# SolderDispenser_v1_0.net
KiCad netlist of a schematic drawn in EAGLE
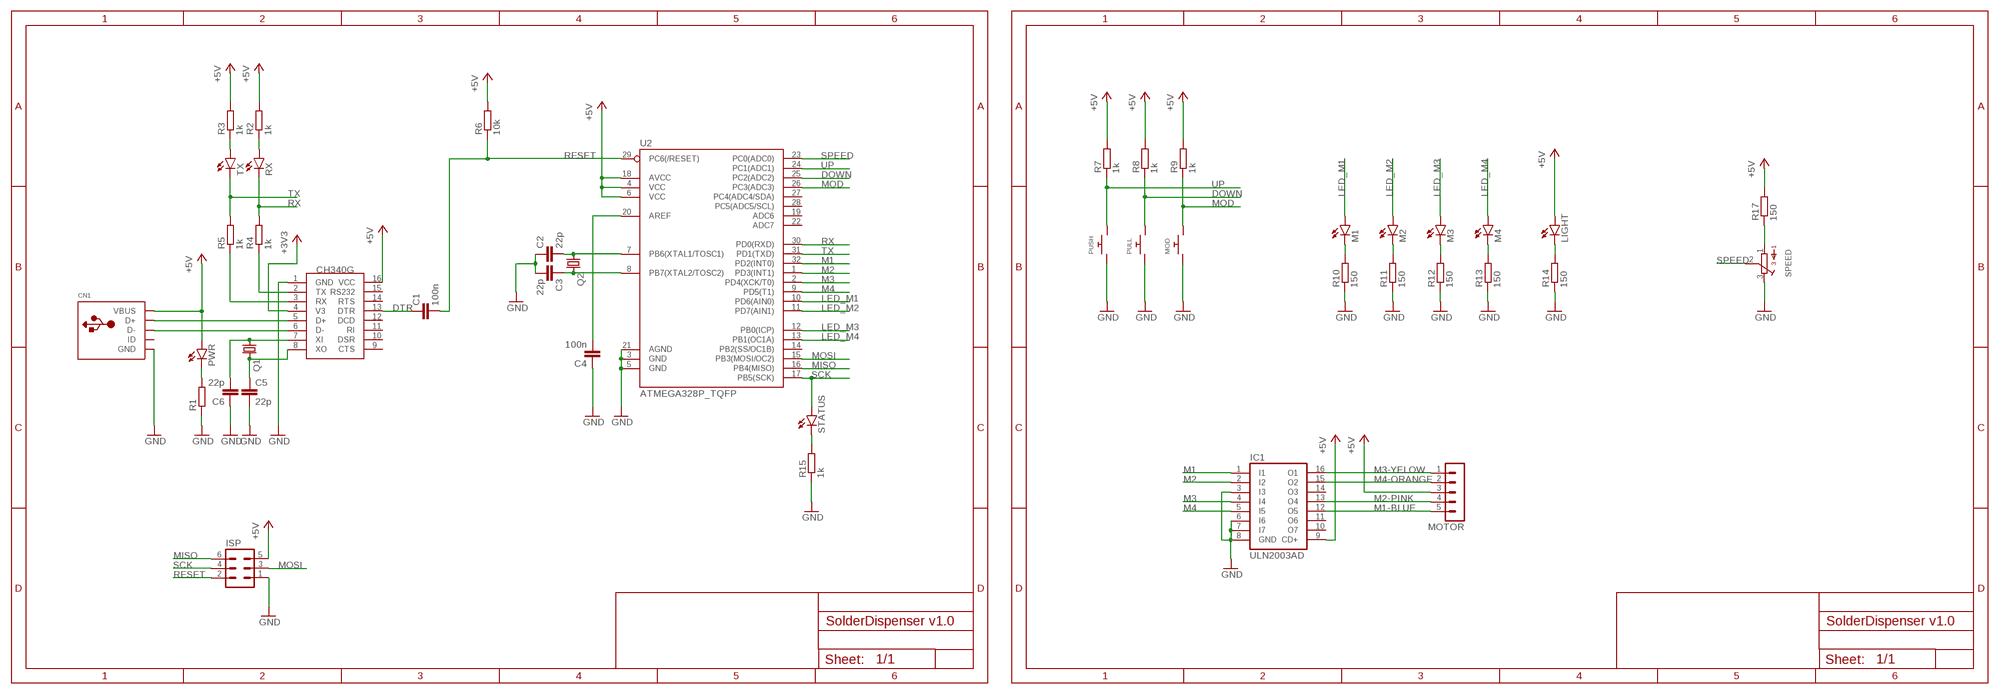
[diagram p0: schematic, sheet 1]

(export (version "E")
  (design (tool "Eeschema 10.0.6"))
  (components
    (comp (ref "C1")
      (value "100n")
      (footprint "eagle-import:C0805")
      (libsource (lib "eagle-import") (part "C-EUC0805"))
    )
    (comp (ref "C2")
      (value "22p")
      (footprint "eagle-import:C0805")
      (libsource (lib "eagle-import") (part "C-EUC0805"))
    )
    (comp (ref "C3")
      (value "22p")
      (footprint "eagle-import:C0805")
      (libsource (lib "eagle-import") (part "C-EUC0805"))
    )
    (comp (ref "C4")
      (value "100n")
      (footprint "eagle-import:C0805")
      (libsource (lib "eagle-import") (part "C-EUC0805"))
    )
    (comp (ref "C5")
      (value "22p")
      (footprint "eagle-import:C0805")
      (libsource (lib "eagle-import") (part "C-EUC0805"))
    )
    (comp (ref "C6")
      (value "22p")
      (footprint "eagle-import:C0805")
      (libsource (lib "eagle-import") (part "C-EUC0805"))
    )
    (comp (ref "CN1")
      (value "USBMOLEX")
      (footprint "eagle-import:USB-MINIB-THM-MOLEX")
      (libsource (lib "eagle-import") (part "USBMOLEX"))
    )
    (comp (ref "IC1")
      (value "ULN2003AD")
      (footprint "eagle-import:SO16")
      (libsource (lib "eagle-import") (part "ULN2003AD"))
    )
    (comp (ref "ISP")
      (value "MA03-2")
      (footprint "eagle-import:MA03-2")
      (libsource (lib "eagle-import") (part "MA03-2"))
    )
    (comp (ref "LIGHT")
      (value "LED5MM")
      (footprint "eagle-import:LED5MM")
      (libsource (lib "eagle-import") (part "LED5MM"))
    )
    (comp (ref "M1")
      (value "LEDSML0805")
      (footprint "eagle-import:SML0805")
      (libsource (lib "eagle-import") (part "LEDSML0805"))
    )
    (comp (ref "M2")
      (value "LEDSML0805")
      (footprint "eagle-import:SML0805")
      (libsource (lib "eagle-import") (part "LEDSML0805"))
    )
    (comp (ref "M3")
      (value "LEDSML0805")
      (footprint "eagle-import:SML0805")
      (libsource (lib "eagle-import") (part "LEDSML0805"))
    )
    (comp (ref "M4")
      (value "LEDSML0805")
      (footprint "eagle-import:SML0805")
      (libsource (lib "eagle-import") (part "LEDSML0805"))
    )
    (comp (ref "MOD")
      (value "SWITCH_PUSHBUTTONEVQ-PE")
      (footprint "eagle-import:TACT_PANA-EVQ")
      (libsource (lib "eagle-import") (part "SWITCH_PUSHBUTTONEVQ-PE"))
    )
    (comp (ref "MOTOR")
      (value "MA05-1")
      (footprint "eagle-import:MA05-1")
      (libsource (lib "eagle-import") (part "MA05-1"))
    )
    (comp (ref "PULL")
      (value "SWITCH_PUSHBUTTONEVQ-PE")
      (footprint "eagle-import:TACT_PANA-EVQ")
      (libsource (lib "eagle-import") (part "SWITCH_PUSHBUTTONEVQ-PE"))
    )
    (comp (ref "PUSH")
      (value "SWITCH_PUSHBUTTONEVQ-PE")
      (footprint "eagle-import:TACT_PANA-EVQ")
      (libsource (lib "eagle-import") (part "SWITCH_PUSHBUTTONEVQ-PE"))
    )
    (comp (ref "PWR")
      (value "LEDSML0805")
      (footprint "eagle-import:SML0805")
      (libsource (lib "eagle-import") (part "LEDSML0805"))
    )
    (comp (ref "Q1")
      (value "CRYSTALHC49UP")
      (footprint "eagle-import:HC49UP")
      (libsource (lib "eagle-import") (part "CRYSTALHC49UP"))
    )
    (comp (ref "Q2")
      (value "CRYSTALHC49UP")
      (footprint "eagle-import:HC49UP")
      (libsource (lib "eagle-import") (part "CRYSTALHC49UP"))
    )
    (comp (ref "R1")
      (value "R-EU_R0805")
      (footprint "eagle-import:R0805")
      (libsource (lib "eagle-import") (part "R-EU_R0805"))
    )
    (comp (ref "R2")
      (value "1k")
      (footprint "eagle-import:R0805")
      (libsource (lib "eagle-import") (part "R-EU_R0805"))
    )
    (comp (ref "R3")
      (value "1k")
      (footprint "eagle-import:R0805")
      (libsource (lib "eagle-import") (part "R-EU_R0805"))
    )
    (comp (ref "R4")
      (value "1k")
      (footprint "eagle-import:R0805")
      (libsource (lib "eagle-import") (part "R-EU_R0805"))
    )
    (comp (ref "R5")
      (value "1k")
      (footprint "eagle-import:R0805")
      (libsource (lib "eagle-import") (part "R-EU_R0805"))
    )
    (comp (ref "R6")
      (value "10k")
      (footprint "eagle-import:R0805")
      (libsource (lib "eagle-import") (part "R-EU_R0805"))
    )
    (comp (ref "R7")
      (value "1k")
      (footprint "eagle-import:R0805")
      (libsource (lib "eagle-import") (part "R-EU_R0805"))
    )
    (comp (ref "R8")
      (value "1k")
      (footprint "eagle-import:R0805")
      (libsource (lib "eagle-import") (part "R-EU_R0805"))
    )
    (comp (ref "R9")
      (value "1k")
      (footprint "eagle-import:R0805")
      (libsource (lib "eagle-import") (part "R-EU_R0805"))
    )
    (comp (ref "R10")
      (value "150")
      (footprint "eagle-import:R0805")
      (libsource (lib "eagle-import") (part "R-EU_R0805"))
    )
    (comp (ref "R11")
      (value "150")
      (footprint "eagle-import:R0805")
      (libsource (lib "eagle-import") (part "R-EU_R0805"))
    )
    (comp (ref "R12")
      (value "150")
      (footprint "eagle-import:R0805")
      (libsource (lib "eagle-import") (part "R-EU_R0805"))
    )
    (comp (ref "R13")
      (value "150")
      (footprint "eagle-import:R0805")
      (libsource (lib "eagle-import") (part "R-EU_R0805"))
    )
    (comp (ref "R14")
      (value "150")
      (footprint "eagle-import:R0805")
      (libsource (lib "eagle-import") (part "R-EU_R0805"))
    )
    (comp (ref "R15")
      (value "1k")
      (footprint "eagle-import:R0805")
      (libsource (lib "eagle-import") (part "R-EU_R0805"))
    )
    (comp (ref "R17")
      (value "150")
      (footprint "eagle-import:R0805")
      (libsource (lib "eagle-import") (part "R-EU_R0805"))
    )
    (comp (ref "RX")
      (value "LEDSML0805")
      (footprint "eagle-import:SML0805")
      (libsource (lib "eagle-import") (part "LEDSML0805"))
    )
    (comp (ref "SPEED")
      (value "3362P")
      (footprint "eagle-import:3362P")
      (libsource (lib "eagle-import") (part "3362P"))
    )
    (comp (ref "STATUS")
      (value "LEDSML0805")
      (footprint "eagle-import:SML0805")
      (libsource (lib "eagle-import") (part "LEDSML0805"))
    )
    (comp (ref "TX")
      (value "LEDSML0805")
      (footprint "eagle-import:SML0805")
      (libsource (lib "eagle-import") (part "LEDSML0805"))
    )
    (comp (ref "U$1")
      (value "CH340G")
      (footprint "eagle-import:SOIC16")
      (libsource (lib "eagle-import") (part "CH340G"))
    )
    (comp (ref "U2")
      (value "ATMEGA328P_TQFP")
      (footprint "eagle-import:TQFP32-08")
      (libsource (lib "eagle-import") (part "ATMEGA328P_TQFP"))
    )
  )
  (nets
    (net (code "1") (name "+3V3") (class "Default")
      (node (ref "U$1") (pin "4") (pinfunction "V3_4") (pintype "bidirectional"))
    )
    (net (code "2") (name "+5V") (class "Default")
      (node (ref "CN1") (pin "VBUS") (pinfunction "VBUS_VBUS") (pintype "power_in"))
      (node (ref "IC1") (pin "9") (pinfunction "CD+_9") (pintype "passive"))
      (node (ref "ISP") (pin "5") (pinfunction "5_5") (pintype "passive"))
      (node (ref "LIGHT") (pin "A") (pinfunction "A_A") (pintype "passive"))
      (node (ref "MOTOR") (pin "3") (pinfunction "3_3") (pintype "passive"))
      (node (ref "PWR") (pin "A") (pinfunction "A_A") (pintype "passive"))
      (node (ref "R17") (pin "2") (pinfunction "2_2") (pintype "passive"))
      (node (ref "R2") (pin "2") (pinfunction "2_2") (pintype "passive"))
      (node (ref "R3") (pin "2") (pinfunction "2_2") (pintype "passive"))
      (node (ref "R6") (pin "2") (pinfunction "2_2") (pintype "passive"))
      (node (ref "R7") (pin "2") (pinfunction "2_2") (pintype "passive"))
      (node (ref "R8") (pin "2") (pinfunction "2_2") (pintype "passive"))
      (node (ref "R9") (pin "2") (pinfunction "2_2") (pintype "passive"))
      (node (ref "U$1") (pin "16") (pinfunction "VCC_16") (pintype "bidirectional"))
      (node (ref "U2") (pin "18") (pinfunction "AVCC_18") (pintype "bidirectional"))
      (node (ref "U2") (pin "4") (pinfunction "VCC_4") (pintype "bidirectional"))
      (node (ref "U2") (pin "6") (pinfunction "VCC_6") (pintype "bidirectional"))
    )
    (net (code "3") (name "/DOWN") (class "Default")
      (node (ref "PULL") (pin "P$2") (pinfunction "P$2_P$2") (pintype "passive"))
      (node (ref "R8") (pin "1") (pinfunction "1_1") (pintype "passive"))
      (node (ref "U2") (pin "25") (pinfunction "PC2(ADC2)_25") (pintype "bidirectional"))
    )
    (net (code "4") (name "/DTR") (class "Default")
      (node (ref "C1") (pin "1") (pinfunction "1_1") (pintype "passive"))
      (node (ref "U$1") (pin "13") (pinfunction "DTR_13") (pintype "bidirectional"))
    )
    (net (code "5") (name "/LED_M1") (class "Default")
      (node (ref "M1") (pin "A") (pinfunction "A_A") (pintype "passive"))
      (node (ref "U2") (pin "10") (pinfunction "PD6(AIN0)_10") (pintype "bidirectional"))
    )
    (net (code "6") (name "/LED_M2") (class "Default")
      (node (ref "M2") (pin "A") (pinfunction "A_A") (pintype "passive"))
      (node (ref "U2") (pin "11") (pinfunction "PD7(AIN1)_11") (pintype "bidirectional"))
    )
    (net (code "7") (name "/LED_M3") (class "Default")
      (node (ref "M3") (pin "A") (pinfunction "A_A") (pintype "passive"))
      (node (ref "U2") (pin "12") (pinfunction "PB0(ICP)_12") (pintype "bidirectional"))
    )
    (net (code "8") (name "/LED_M4") (class "Default")
      (node (ref "M4") (pin "A") (pinfunction "A_A") (pintype "passive"))
      (node (ref "U2") (pin "13") (pinfunction "PB1(OC1A)_13") (pintype "bidirectional"))
    )
    (net (code "9") (name "/M1") (class "Default")
      (node (ref "IC1") (pin "1") (pinfunction "I1_1") (pintype "input"))
      (node (ref "U2") (pin "32") (pinfunction "PD2(INT0)_32") (pintype "bidirectional"))
    )
    (net (code "10") (name "/M1-BLUE") (class "Default")
      (node (ref "IC1") (pin "12") (pinfunction "O5_12") (pintype "open_collector"))
      (node (ref "MOTOR") (pin "5") (pinfunction "5_5") (pintype "passive"))
    )
    (net (code "11") (name "/M2") (class "Default")
      (node (ref "IC1") (pin "2") (pinfunction "I2_2") (pintype "input"))
      (node (ref "U2") (pin "1") (pinfunction "PD3(INT1)_1") (pintype "bidirectional"))
    )
    (net (code "12") (name "/M2-PINK") (class "Default")
      (node (ref "IC1") (pin "13") (pinfunction "O4_13") (pintype "open_collector"))
      (node (ref "MOTOR") (pin "4") (pinfunction "4_4") (pintype "passive"))
    )
    (net (code "13") (name "/M3") (class "Default")
      (node (ref "IC1") (pin "4") (pinfunction "I4_4") (pintype "input"))
      (node (ref "U2") (pin "2") (pinfunction "PD4(XCK/T0)_2") (pintype "bidirectional"))
    )
    (net (code "14") (name "/M3-YELOW") (class "Default")
      (node (ref "IC1") (pin "16") (pinfunction "O1_16") (pintype "open_collector"))
      (node (ref "MOTOR") (pin "1") (pinfunction "1_1") (pintype "passive"))
    )
    (net (code "15") (name "/M4") (class "Default")
      (node (ref "IC1") (pin "5") (pinfunction "I5_5") (pintype "input"))
      (node (ref "U2") (pin "9") (pinfunction "PD5(T1)_9") (pintype "bidirectional"))
    )
    (net (code "16") (name "/M4-ORANGE") (class "Default")
      (node (ref "IC1") (pin "15") (pinfunction "O2_15") (pintype "open_collector"))
      (node (ref "MOTOR") (pin "2") (pinfunction "2_2") (pintype "passive"))
    )
    (net (code "17") (name "/MISO") (class "Default")
      (node (ref "ISP") (pin "6") (pinfunction "6_6") (pintype "passive"))
      (node (ref "U2") (pin "16") (pinfunction "PB4(MISO)_16") (pintype "bidirectional"))
    )
    (net (code "18") (name "/MOD") (class "Default")
      (node (ref "MOD") (pin "P$2") (pinfunction "P$2_P$2") (pintype "passive"))
      (node (ref "R9") (pin "1") (pinfunction "1_1") (pintype "passive"))
      (node (ref "U2") (pin "26") (pinfunction "PC3(ADC3)_26") (pintype "bidirectional"))
    )
    (net (code "19") (name "/MOSI") (class "Default")
      (node (ref "ISP") (pin "3") (pinfunction "3_3") (pintype "passive"))
      (node (ref "U2") (pin "15") (pinfunction "PB3(MOSI/OC2)_15") (pintype "bidirectional"))
    )
    (net (code "20") (name "/RESET") (class "Default")
      (node (ref "C1") (pin "2") (pinfunction "2_2") (pintype "passive"))
      (node (ref "ISP") (pin "2") (pinfunction "2_2") (pintype "passive"))
      (node (ref "R6") (pin "1") (pinfunction "1_1") (pintype "passive"))
      (node (ref "U2") (pin "29") (pinfunction "PC6(/RESET)_29") (pintype "bidirectional"))
    )
    (net (code "21") (name "/RX") (class "Default")
      (node (ref "R4") (pin "2") (pinfunction "2_2") (pintype "passive"))
      (node (ref "RX") (pin "C") (pinfunction "C_C") (pintype "passive"))
      (node (ref "U2") (pin "30") (pinfunction "PD0(RXD)_30") (pintype "bidirectional"))
    )
    (net (code "22") (name "/SCK") (class "Default")
      (node (ref "ISP") (pin "4") (pinfunction "4_4") (pintype "passive"))
      (node (ref "STATUS") (pin "A") (pinfunction "A_A") (pintype "passive"))
      (node (ref "U2") (pin "17") (pinfunction "PB5(SCK)_17") (pintype "bidirectional"))
    )
    (net (code "23") (name "/SPEED") (class "Default")
      (node (ref "SPEED") (pin "2") (pinfunction "2_2") (pintype "passive"))
      (node (ref "U2") (pin "23") (pinfunction "PC0(ADC0)_23") (pintype "bidirectional"))
    )
    (net (code "24") (name "/TX") (class "Default")
      (node (ref "R5") (pin "2") (pinfunction "2_2") (pintype "passive"))
      (node (ref "TX") (pin "C") (pinfunction "C_C") (pintype "passive"))
      (node (ref "U2") (pin "31") (pinfunction "PD1(TXD)_31") (pintype "bidirectional"))
    )
    (net (code "25") (name "/UP") (class "Default")
      (node (ref "PUSH") (pin "P$2") (pinfunction "P$2_P$2") (pintype "passive"))
      (node (ref "R7") (pin "1") (pinfunction "1_1") (pintype "passive"))
      (node (ref "U2") (pin "24") (pinfunction "PC1(ADC1)_24") (pintype "bidirectional"))
    )
    (net (code "26") (name "GND") (class "Default")
      (node (ref "C2") (pin "1") (pinfunction "1_1") (pintype "passive"))
      (node (ref "C3") (pin "2") (pinfunction "2_2") (pintype "passive"))
      (node (ref "C4") (pin "1") (pinfunction "1_1") (pintype "passive"))
      (node (ref "C5") (pin "2") (pinfunction "2_2") (pintype "passive"))
      (node (ref "C6") (pin "1") (pinfunction "1_1") (pintype "passive"))
      (node (ref "CN1") (pin "GND") (pinfunction "GND_GND") (pintype "power_in"))
      (node (ref "IC1") (pin "3") (pinfunction "I3_3") (pintype "input"))
      (node (ref "IC1") (pin "6") (pinfunction "I6_6") (pintype "input"))
      (node (ref "IC1") (pin "7") (pinfunction "I7_7") (pintype "input"))
      (node (ref "IC1") (pin "8") (pinfunction "GND_8") (pintype "power_in"))
      (node (ref "ISP") (pin "1") (pinfunction "1_1") (pintype "passive"))
      (node (ref "MOD") (pin "P$1") (pinfunction "P$1_P$1") (pintype "passive"))
      (node (ref "PULL") (pin "P$1") (pinfunction "P$1_P$1") (pintype "passive"))
      (node (ref "PUSH") (pin "P$1") (pinfunction "P$1_P$1") (pintype "passive"))
      (node (ref "R1") (pin "1") (pinfunction "1_1") (pintype "passive"))
      (node (ref "R10") (pin "1") (pinfunction "1_1") (pintype "passive"))
      (node (ref "R11") (pin "1") (pinfunction "1_1") (pintype "passive"))
      (node (ref "R12") (pin "1") (pinfunction "1_1") (pintype "passive"))
      (node (ref "R13") (pin "1") (pinfunction "1_1") (pintype "passive"))
      (node (ref "R14") (pin "1") (pinfunction "1_1") (pintype "passive"))
      (node (ref "R15") (pin "1") (pinfunction "1_1") (pintype "passive"))
      (node (ref "SPEED") (pin "3") (pinfunction "3_3") (pintype "passive"))
      (node (ref "U$1") (pin "1") (pinfunction "GND_1") (pintype "bidirectional"))
      (node (ref "U2") (pin "21") (pinfunction "AGND_21") (pintype "bidirectional"))
      (node (ref "U2") (pin "3") (pinfunction "GND_3") (pintype "bidirectional"))
      (node (ref "U2") (pin "5") (pinfunction "GND_5") (pintype "bidirectional"))
    )
    (net (code "27") (name "Net-(LIGHT-C)") (class "Default")
      (node (ref "LIGHT") (pin "K") (pinfunction "C_K") (pintype "passive"))
      (node (ref "R14") (pin "2") (pinfunction "2_2") (pintype "passive"))
    )
    (net (code "28") (name "Net-(M1-PadC)") (class "Default")
      (node (ref "M1") (pin "C") (pinfunction "C_C") (pintype "passive"))
      (node (ref "R10") (pin "2") (pinfunction "2_2") (pintype "passive"))
    )
    (net (code "29") (name "Net-(M2-PadC)") (class "Default")
      (node (ref "M2") (pin "C") (pinfunction "C_C") (pintype "passive"))
      (node (ref "R11") (pin "2") (pinfunction "2_2") (pintype "passive"))
    )
    (net (code "30") (name "Net-(M3-PadC)") (class "Default")
      (node (ref "M3") (pin "C") (pinfunction "C_C") (pintype "passive"))
      (node (ref "R12") (pin "2") (pinfunction "2_2") (pintype "passive"))
    )
    (net (code "31") (name "Net-(M4-PadC)") (class "Default")
      (node (ref "M4") (pin "C") (pinfunction "C_C") (pintype "passive"))
      (node (ref "R13") (pin "2") (pinfunction "2_2") (pintype "passive"))
    )
    (net (code "32") (name "Net-(PWR-PadC)") (class "Default")
      (node (ref "PWR") (pin "C") (pinfunction "C_C") (pintype "passive"))
      (node (ref "R1") (pin "2") (pinfunction "2_2") (pintype "passive"))
    )
    (net (code "33") (name "Net-(R2-Pad1)") (class "Default")
      (node (ref "R2") (pin "1") (pinfunction "1_1") (pintype "passive"))
      (node (ref "RX") (pin "A") (pinfunction "A_A") (pintype "passive"))
    )
    (net (code "34") (name "Net-(R3-Pad1)") (class "Default")
      (node (ref "R3") (pin "1") (pinfunction "1_1") (pintype "passive"))
      (node (ref "TX") (pin "A") (pinfunction "A_A") (pintype "passive"))
    )
    (net (code "35") (name "Net-(R15-Pad2)") (class "Default")
      (node (ref "R15") (pin "2") (pinfunction "2_2") (pintype "passive"))
      (node (ref "STATUS") (pin "C") (pinfunction "C_C") (pintype "passive"))
    )
    (net (code "36") (name "Net-(R17-Pad1)") (class "Default")
      (node (ref "R17") (pin "1") (pinfunction "1_1") (pintype "passive"))
      (node (ref "SPEED") (pin "1") (pinfunction "1_1") (pintype "passive"))
    )
    (net (code "37") (name "Net-(U$1-D+)") (class "Default")
      (node (ref "CN1") (pin "D+") (pinfunction "D+_D+") (pintype "bidirectional"))
      (node (ref "U$1") (pin "5") (pinfunction "D+_5") (pintype "bidirectional"))
    )
    (net (code "38") (name "Net-(U$1-D-)") (class "Default")
      (node (ref "CN1") (pin "D-") (pinfunction "D-_D-") (pintype "bidirectional"))
      (node (ref "U$1") (pin "6") (pinfunction "D-_6") (pintype "bidirectional"))
    )
    (net (code "39") (name "Net-(U$1-RX)") (class "Default")
      (node (ref "R5") (pin "1") (pinfunction "1_1") (pintype "passive"))
      (node (ref "U$1") (pin "3") (pinfunction "RX_3") (pintype "bidirectional"))
    )
    (net (code "40") (name "Net-(U$1-TX)") (class "Default")
      (node (ref "R4") (pin "1") (pinfunction "1_1") (pintype "passive"))
      (node (ref "U$1") (pin "2") (pinfunction "TX_2") (pintype "bidirectional"))
    )
    (net (code "41") (name "Net-(U$1-XI)") (class "Default")
      (node (ref "C6") (pin "2") (pinfunction "2_2") (pintype "passive"))
      (node (ref "Q1") (pin "1") (pinfunction "1_1") (pintype "passive"))
      (node (ref "U$1") (pin "7") (pinfunction "XI_7") (pintype "bidirectional"))
    )
    (net (code "42") (name "Net-(U$1-XO)") (class "Default")
      (node (ref "C5") (pin "1") (pinfunction "1_1") (pintype "passive"))
      (node (ref "Q1") (pin "2") (pinfunction "2_2") (pintype "passive"))
      (node (ref "U$1") (pin "8") (pinfunction "XO_8") (pintype "bidirectional"))
    )
    (net (code "43") (name "Net-(U2-AREF)") (class "Default")
      (node (ref "C4") (pin "2") (pinfunction "2_2") (pintype "passive"))
      (node (ref "U2") (pin "20") (pinfunction "AREF_20") (pintype "bidirectional"))
    )
    (net (code "44") (name "Net-(U2-PB6(XTAL1{slash}TOSC1))") (class "Default")
      (node (ref "C2") (pin "2") (pinfunction "2_2") (pintype "passive"))
      (node (ref "Q2") (pin "1") (pinfunction "1_1") (pintype "passive"))
      (node (ref "U2") (pin "7") (pinfunction "PB6(XTAL1/TOSC1)_7") (pintype "bidirectional"))
    )
    (net (code "45") (name "Net-(U2-PB7(XTAL2{slash}TOSC2))") (class "Default")
      (node (ref "C3") (pin "1") (pinfunction "1_1") (pintype "passive"))
      (node (ref "Q2") (pin "2") (pinfunction "2_2") (pintype "passive"))
      (node (ref "U2") (pin "8") (pinfunction "PB7(XTAL2/TOSC2)_8") (pintype "bidirectional"))
    )
    (net (code "46") (name "unconnected-(CN1-PadID)") (class "Default")
      (node (ref "CN1") (pin "ID") (pinfunction "ID_ID") (pintype "bidirectional"))
    )
    (net (code "47") (name "unconnected-(IC1-O3-Pad14)") (class "Default")
      (node (ref "IC1") (pin "14") (pinfunction "O3_14") (pintype "open_collector"))
    )
    (net (code "48") (name "unconnected-(IC1-O6-Pad11)") (class "Default")
      (node (ref "IC1") (pin "11") (pinfunction "O6_11") (pintype "open_collector"))
    )
    (net (code "49") (name "unconnected-(IC1-O7-Pad10)") (class "Default")
      (node (ref "IC1") (pin "10") (pinfunction "O7_10") (pintype "open_collector"))
    )
    (net (code "50") (name "unconnected-(U$1-CTS-Pad9)") (class "Default")
      (node (ref "U$1") (pin "9") (pinfunction "CTS_9") (pintype "bidirectional"))
    )
    (net (code "51") (name "unconnected-(U$1-DCD-Pad12)") (class "Default")
      (node (ref "U$1") (pin "12") (pinfunction "DCD_12") (pintype "bidirectional"))
    )
    (net (code "52") (name "unconnected-(U$1-DSR-Pad10)") (class "Default")
      (node (ref "U$1") (pin "10") (pinfunction "DSR_10") (pintype "bidirectional"))
    )
    (net (code "53") (name "unconnected-(U$1-RI-Pad11)") (class "Default")
      (node (ref "U$1") (pin "11") (pinfunction "RI_11") (pintype "bidirectional"))
    )
    (net (code "54") (name "unconnected-(U$1-RS232-Pad15)") (class "Default")
      (node (ref "U$1") (pin "15") (pinfunction "RS232_15") (pintype "bidirectional"))
    )
    (net (code "55") (name "unconnected-(U$1-RTS-Pad14)") (class "Default")
      (node (ref "U$1") (pin "14") (pinfunction "RTS_14") (pintype "bidirectional"))
    )
    (net (code "56") (name "unconnected-(U2-ADC6-Pad19)") (class "Default")
      (node (ref "U2") (pin "19") (pinfunction "ADC6_19") (pintype "bidirectional"))
    )
    (net (code "57") (name "unconnected-(U2-ADC7-Pad22)") (class "Default")
      (node (ref "U2") (pin "22") (pinfunction "ADC7_22") (pintype "bidirectional"))
    )
    (net (code "58") (name "unconnected-(U2-PB2(SS{slash}OC1B)-Pad14)") (class "Default")
      (node (ref "U2") (pin "14") (pinfunction "PB2(SS/OC1B)_14") (pintype "bidirectional"))
    )
    (net (code "59") (name "unconnected-(U2-PC4(ADC4{slash}SDA)-Pad27)") (class "Default")
      (node (ref "U2") (pin "27") (pinfunction "PC4(ADC4/SDA)_27") (pintype "bidirectional"))
    )
    (net (code "60") (name "unconnected-(U2-PC5(ADC5{slash}SCL)-Pad28)") (class "Default")
      (node (ref "U2") (pin "28") (pinfunction "PC5(ADC5/SCL)_28") (pintype "bidirectional"))
    )
  )
)
